# MainPartSCH.net
KiCad netlist of a schematic drawn in Altium Designer
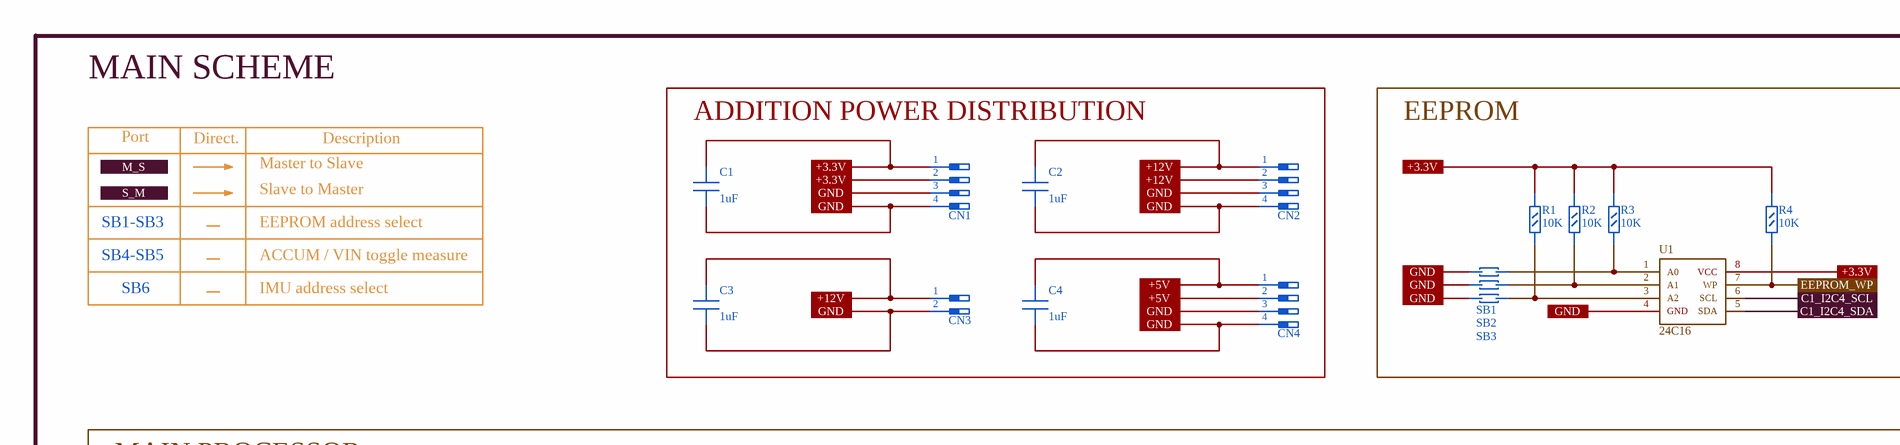
[diagram p0: MainPartSCH.SchDoc, top left]
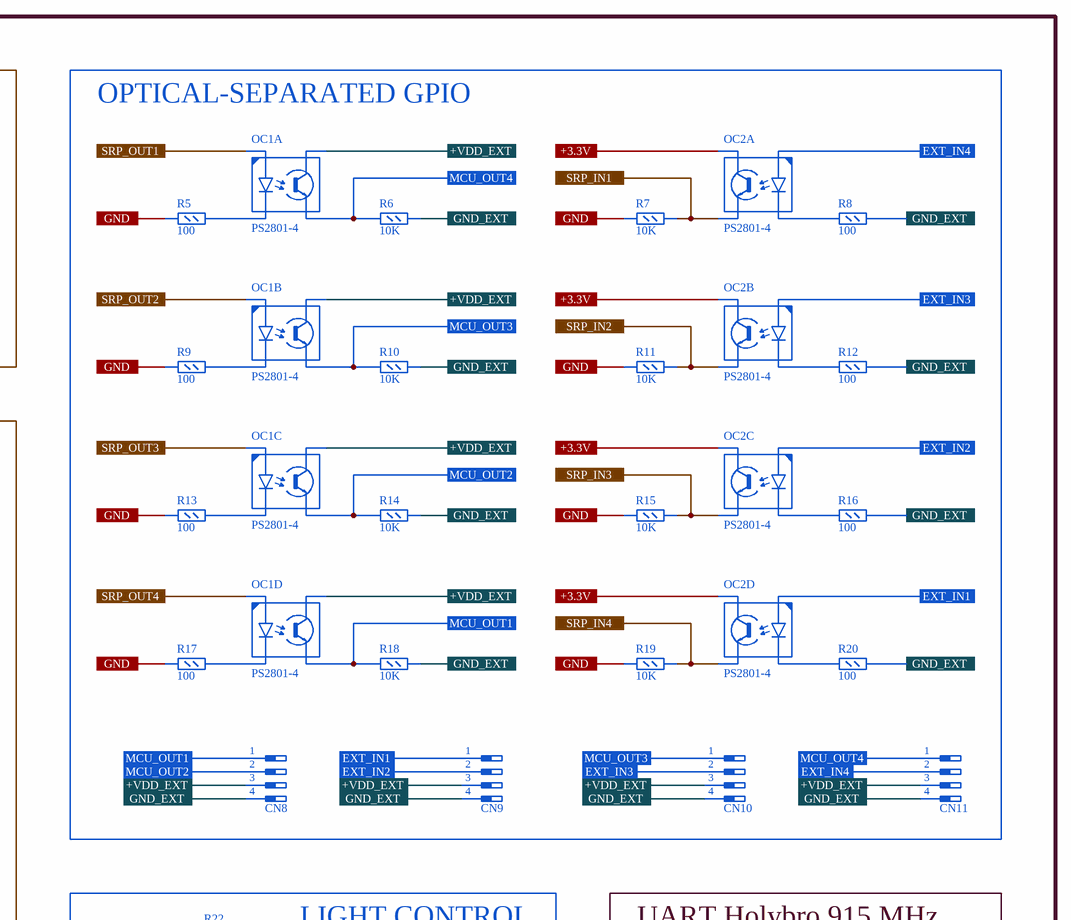
[diagram p1: MainPartSCH.SchDoc, top right]
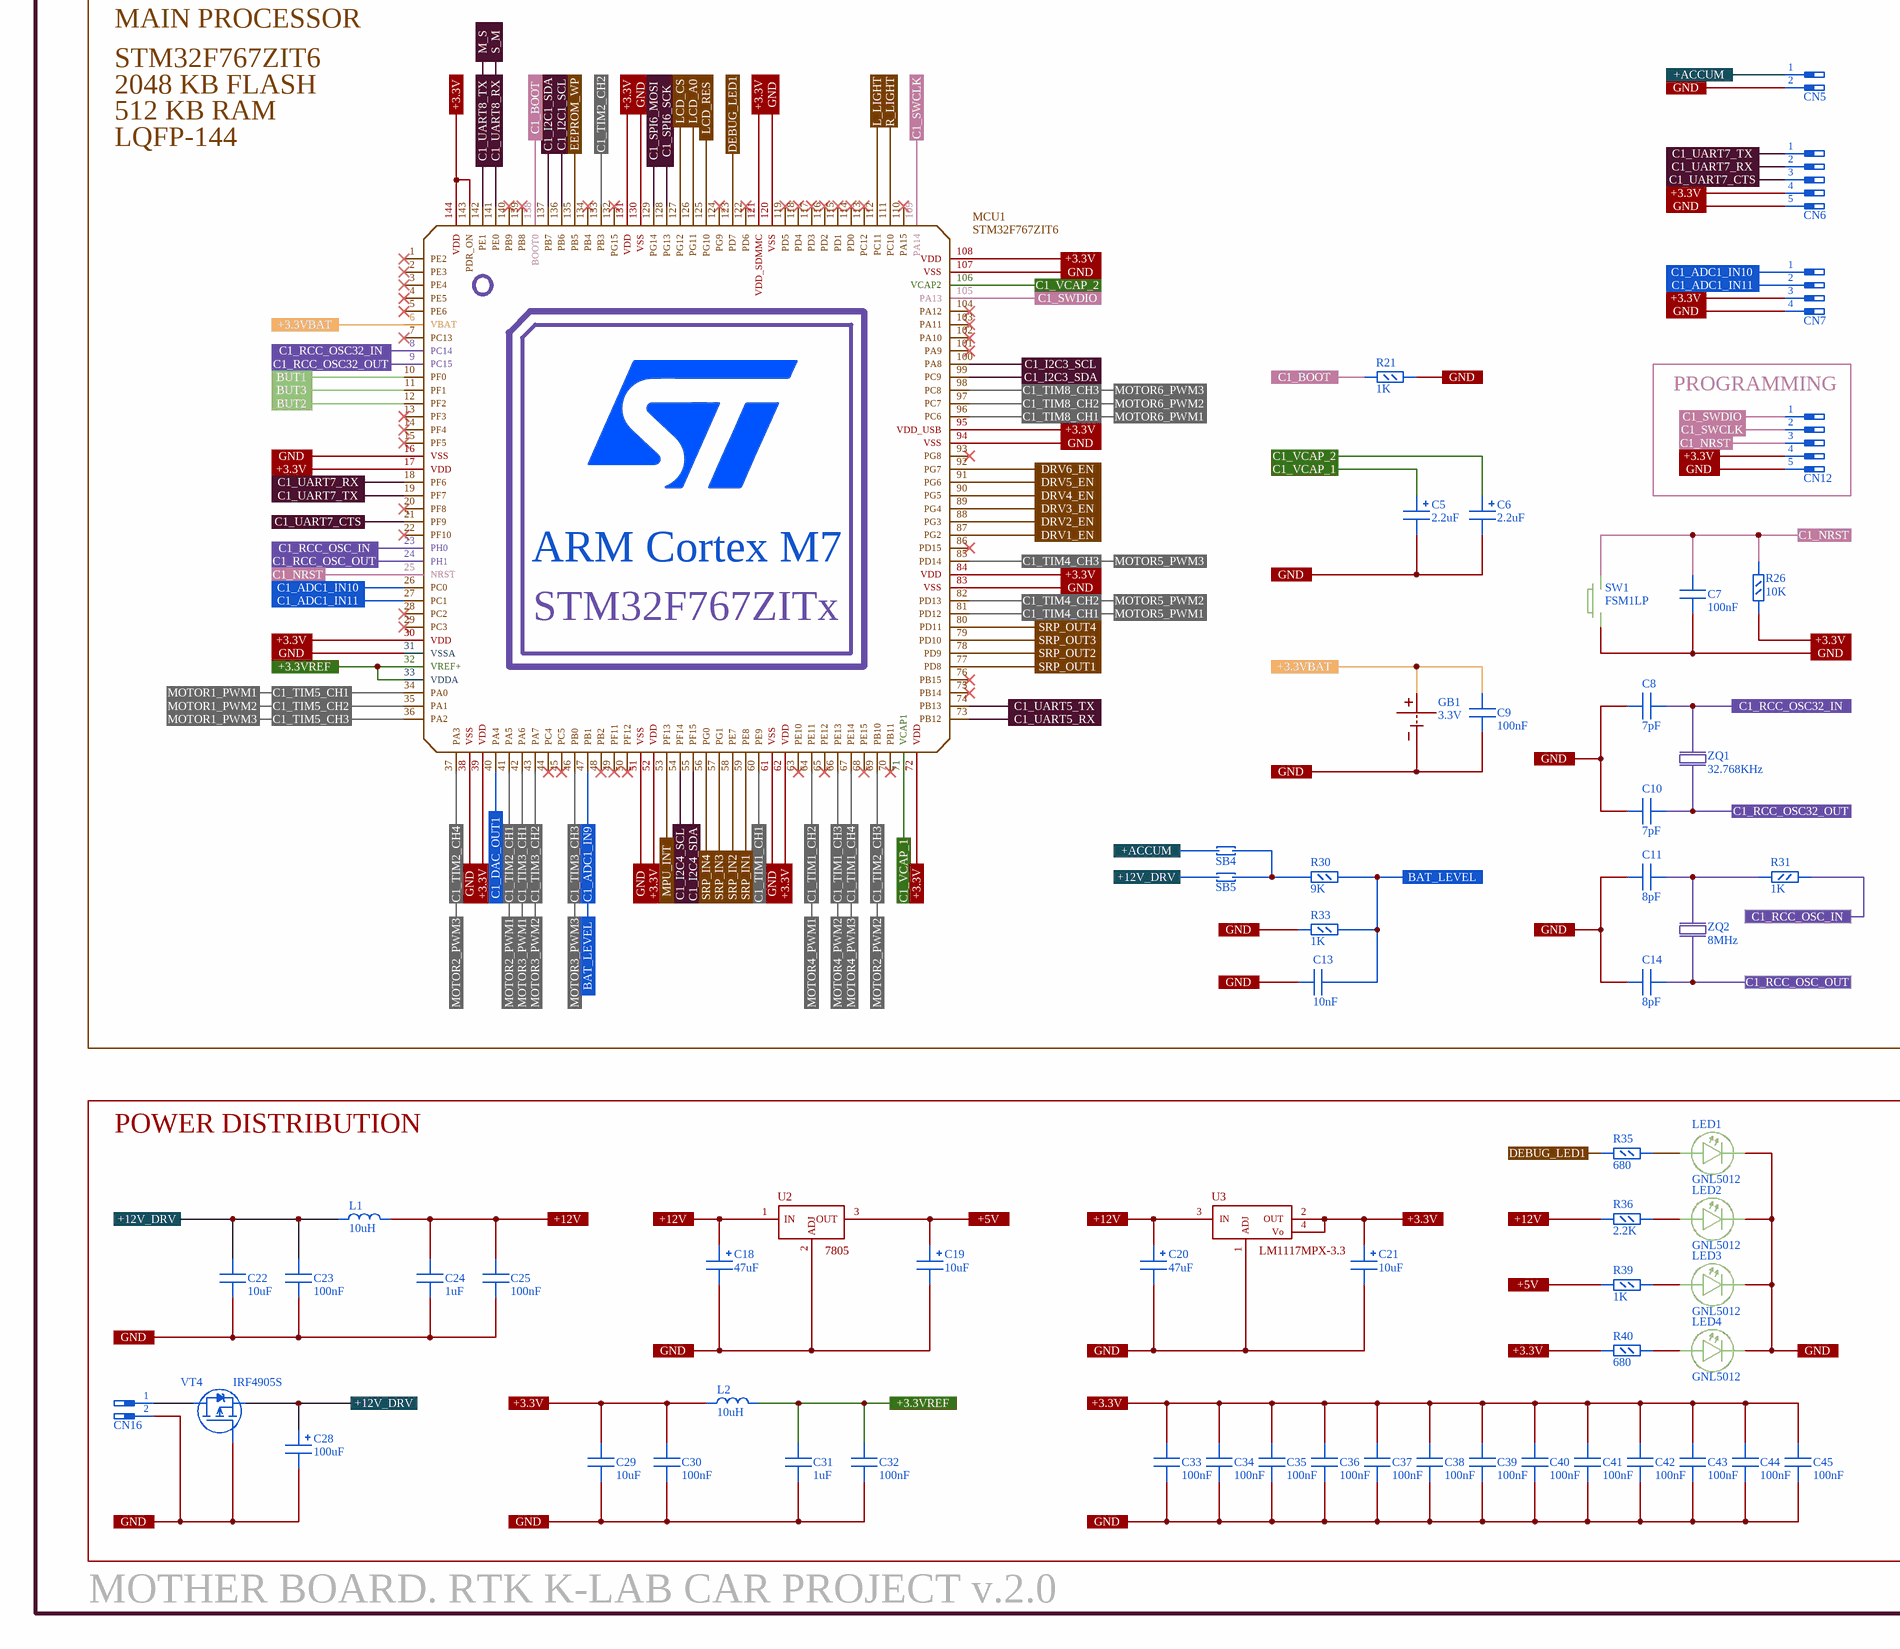
[diagram p2: MainPartSCH.SchDoc, bottom left]
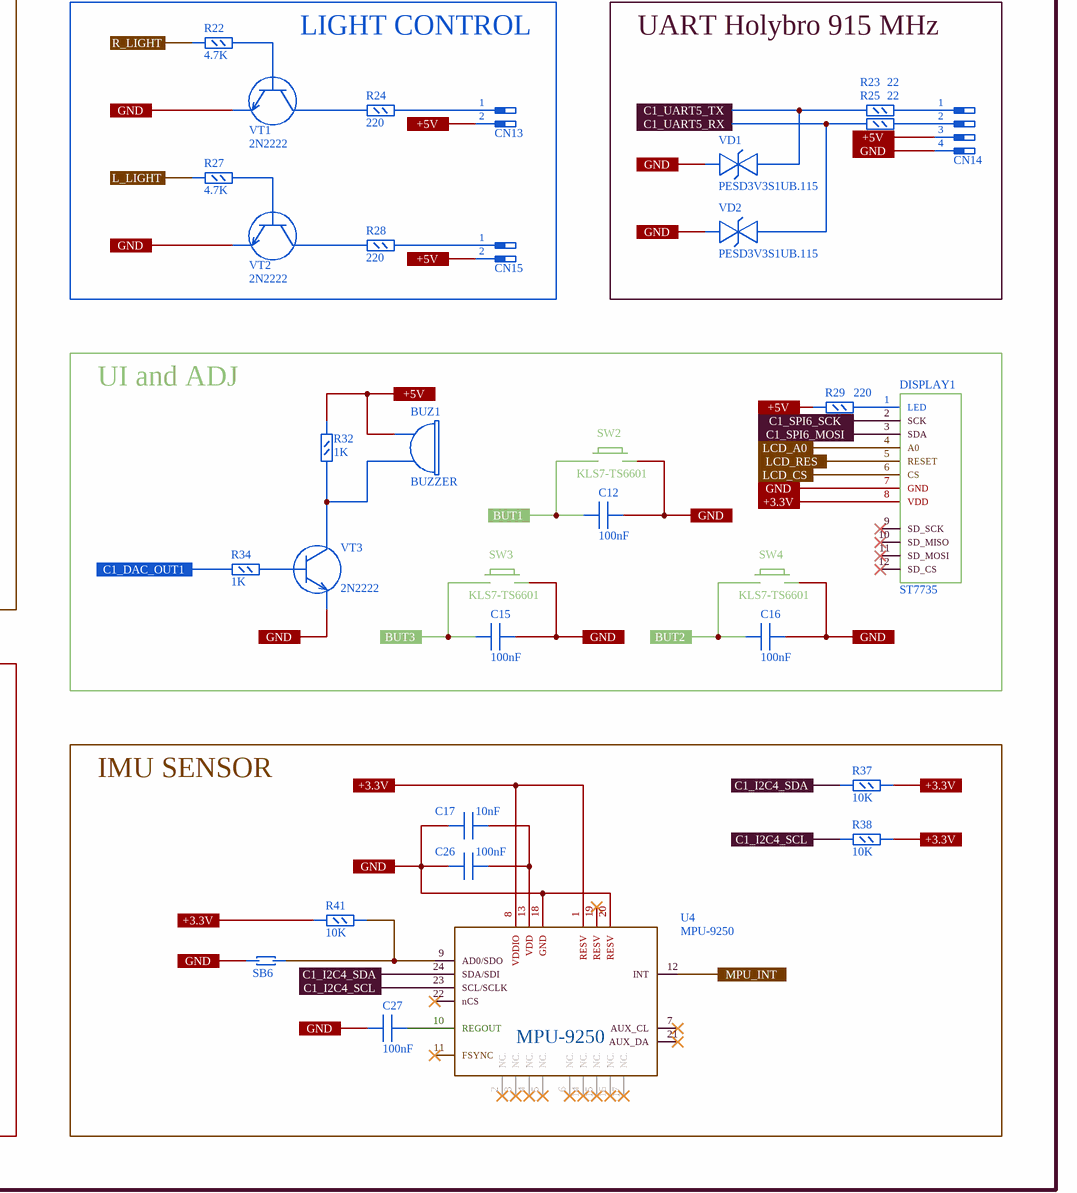
[diagram p3: MainPartSCH.SchDoc, bottom right]

(export (version "E")
  (design (tool "Eeschema 10.0.6"))
  (components
    (comp (ref "BUZ1")
      (value "BUZZER")
      (footprint "BUZZER-5.08MM-D10.5MM")
      (libsource (lib "CommonElements") (part "Buzzer"))
    )
    (comp (ref "C1") (value "1uF") (footprint "C0805") (libsource (lib "CommonElements") (part "Cap")))
    (comp (ref "C2") (value "1uF") (footprint "C0805") (libsource (lib "CommonElements") (part "Cap")))
    (comp (ref "C3") (value "1uF") (footprint "C0805") (libsource (lib "CommonElements") (part "Cap")))
    (comp (ref "C4") (value "1uF") (footprint "C0805") (libsource (lib "CommonElements") (part "Cap")))
    (comp (ref "C5")
      (value "2.2uF")
      (footprint "CAP_TAN-A")
      (libsource (lib "CustomMillLib_Col") (part "Cap_Pol"))
    )
    (comp (ref "C6")
      (value "2.2uF")
      (footprint "CAP_TAN-A")
      (libsource (lib "CustomMillLib_Col") (part "Cap_Pol"))
    )
    (comp (ref "C7") (value "100nF") (footprint "C0603") (libsource (lib "CommonElements") (part "Cap")))
    (comp (ref "C8") (value "7pF") (footprint "C0402") (libsource (lib "CommonElements") (part "Cap")))
    (comp (ref "C9") (value "100nF") (footprint "C0603") (libsource (lib "CommonElements") (part "Cap")))
    (comp (ref "C10") (value "7pF") (footprint "C0402") (libsource (lib "CommonElements") (part "Cap")))
    (comp (ref "C11") (value "8pF") (footprint "C0402") (libsource (lib "CommonElements") (part "Cap")))
    (comp (ref "C12") (value "100nF") (footprint "C0603") (libsource (lib "CommonElements") (part "Cap")))
    (comp (ref "C13") (value "10nF") (footprint "C0603") (libsource (lib "CommonElements") (part "Cap")))
    (comp (ref "C14") (value "8pF") (footprint "C0402") (libsource (lib "CommonElements") (part "Cap")))
    (comp (ref "C15") (value "100nF") (footprint "C0603") (libsource (lib "CommonElements") (part "Cap")))
    (comp (ref "C16") (value "100nF") (footprint "C0603") (libsource (lib "CommonElements") (part "Cap")))
    (comp (ref "C17") (value "10nF") (footprint "C0603") (libsource (lib "CommonElements") (part "Cap")))
    (comp (ref "C18")
      (value "47uF")
      (footprint "CAP_ALSMD-6.3x5.4MM")
      (libsource (lib "CommonElements") (part "Cap Pol"))
    )
    (comp (ref "C19")
      (value "10uF")
      (footprint "CAP_ALSMD-4X5.4MM")
      (libsource (lib "CommonElements") (part "Cap Pol"))
    )
    (comp (ref "C20")
      (value "47uF")
      (footprint "CAP_ALSMD-6.3x5.4MM")
      (libsource (lib "CommonElements") (part "Cap Pol"))
    )
    (comp (ref "C21")
      (value "10uF")
      (footprint "CAP_ALSMD-4X5.4MM")
      (libsource (lib "CommonElements") (part "Cap Pol"))
    )
    (comp (ref "C22") (value "10uF") (footprint "C0805") (libsource (lib "CommonElements") (part "Cap")))
    (comp (ref "C23") (value "100nF") (footprint "C0603") (libsource (lib "CommonElements") (part "Cap")))
    (comp (ref "C24") (value "1uF") (footprint "C0805") (libsource (lib "CommonElements") (part "Cap")))
    (comp (ref "C25") (value "100nF") (footprint "C0603") (libsource (lib "CommonElements") (part "Cap")))
    (comp (ref "C26") (value "100nF") (footprint "C0603") (libsource (lib "CommonElements") (part "Cap")))
    (comp (ref "C27") (value "100nF") (footprint "C0603") (libsource (lib "CommonElements") (part "Cap")))
    (comp (ref "C28")
      (value "100uF")
      (footprint "CAP_ALSMD-8X10.5MM")
      (libsource (lib "CommonElements") (part "Cap Pol"))
    )
    (comp (ref "C29") (value "10uF") (footprint "C0805") (libsource (lib "CommonElements") (part "Cap")))
    (comp (ref "C30") (value "100nF") (footprint "C0603") (libsource (lib "CommonElements") (part "Cap")))
    (comp (ref "C31") (value "1uF") (footprint "C0805") (libsource (lib "CommonElements") (part "Cap")))
    (comp (ref "C32") (value "100nF") (footprint "C0603") (libsource (lib "CommonElements") (part "Cap")))
    (comp (ref "C33") (value "100nF") (footprint "C0603") (libsource (lib "CommonElements") (part "Cap")))
    (comp (ref "C34") (value "100nF") (footprint "C0603") (libsource (lib "CommonElements") (part "Cap")))
    (comp (ref "C35") (value "100nF") (footprint "C0603") (libsource (lib "CommonElements") (part "Cap")))
    (comp (ref "C36") (value "100nF") (footprint "C0603") (libsource (lib "CommonElements") (part "Cap")))
    (comp (ref "C37") (value "100nF") (footprint "C0603") (libsource (lib "CommonElements") (part "Cap")))
    (comp (ref "C38") (value "100nF") (footprint "C0603") (libsource (lib "CommonElements") (part "Cap")))
    (comp (ref "C39") (value "100nF") (footprint "C0603") (libsource (lib "CommonElements") (part "Cap")))
    (comp (ref "C40") (value "100nF") (footprint "C0603") (libsource (lib "CommonElements") (part "Cap")))
    (comp (ref "C41") (value "100nF") (footprint "C0603") (libsource (lib "CommonElements") (part "Cap")))
    (comp (ref "C42") (value "100nF") (footprint "C0603") (libsource (lib "CommonElements") (part "Cap")))
    (comp (ref "C43") (value "100nF") (footprint "C0603") (libsource (lib "CommonElements") (part "Cap")))
    (comp (ref "C44") (value "100nF") (footprint "C0603") (libsource (lib "CommonElements") (part "Cap")))
    (comp (ref "C45") (value "100nF") (footprint "C0603") (libsource (lib "CommonElements") (part "Cap")))
    (comp (ref "CN1") (value "1x04") (footprint "XH2.54-4PIN") (libsource (lib "Connectors") (part "1x04")))
    (comp (ref "CN2") (value "1x04") (footprint "XH2.54-4PIN") (libsource (lib "Connectors") (part "1x04")))
    (comp (ref "CN3") (value "1x02") (footprint "XH2.54-2PIN") (libsource (lib "Connectors") (part "1x02")))
    (comp (ref "CN4") (value "1x04") (footprint "XH2.54-4PIN") (libsource (lib "Connectors") (part "1x04")))
    (comp (ref "CN5") (value "1x02") (footprint "2X1F") (libsource (lib "Connectors") (part "1x02")))
    (comp (ref "CN6") (value "1x05") (footprint "5X1F") (libsource (lib "Connectors") (part "1x05")))
    (comp (ref "CN7") (value "1x04") (footprint "4X1F") (libsource (lib "Connectors") (part "1x04")))
    (comp (ref "CN8") (value "1x04") (footprint "XH2.54-4PIN") (libsource (lib "Connectors") (part "1x04")))
    (comp (ref "CN9") (value "1x04") (footprint "XH2.54-4PIN") (libsource (lib "Connectors") (part "1x04")))
    (comp (ref "CN10") (value "1x04") (footprint "XH2.54-4PIN") (libsource (lib "Connectors") (part "1x04")))
    (comp (ref "CN11") (value "1x04") (footprint "XH2.54-4PIN") (libsource (lib "Connectors") (part "1x04")))
    (comp (ref "CN12") (value "1x05") (footprint "5X1M") (libsource (lib "Connectors") (part "1x05")))
    (comp (ref "CN13") (value "1x02") (footprint "2X1F") (libsource (lib "Connectors") (part "1x02")))
    (comp (ref "CN14") (value "1x04") (footprint "XH2.54-4PIN") (libsource (lib "Connectors") (part "1x04")))
    (comp (ref "CN15") (value "1x02") (footprint "2X1F") (libsource (lib "Connectors") (part "1x02")))
    (comp (ref "CN16") (value "1x02") (footprint "H2-5.08") (libsource (lib "Connectors") (part "1x02")))
    (comp (ref "DISPLAY1")
      (value "ST7735")
      (footprint "8X1M")
      (description "120x160 LCD Display")
      (libsource (lib "OtherEquipmentLib_Col") (part "ST7735 SPI Display + SD Card"))
    )
    (comp (ref "GB1")
      (value "3.3V")
      (footprint "CR1616-SMD")
      (libsource (lib "PowerSupplies_Col") (part "Battery"))
    )
    (comp (ref "L1") (value "10uH") (footprint "L1206") (libsource (lib "CommonElements") (part "Inductor")))
    (comp (ref "L2") (value "10uH") (footprint "L0805") (libsource (lib "CommonElements") (part "Inductor")))
    (comp (ref "LED1")
      (value "GNL5012")
      (footprint "LED0603")
      (libsource (lib "CommonElements") (part "LED"))
    )
    (comp (ref "LED2")
      (value "GNL5012")
      (footprint "LED0603")
      (libsource (lib "CommonElements") (part "LED"))
    )
    (comp (ref "LED3")
      (value "GNL5012")
      (footprint "LED0603")
      (libsource (lib "CommonElements") (part "LED"))
    )
    (comp (ref "LED4")
      (value "GNL5012")
      (footprint "LED0603")
      (libsource (lib "CommonElements") (part "LED"))
    )
    (comp (ref "MCU1")
      (value "STM32F767ZIT6")
      (footprint "LQFP144")
      (libsource (lib "STM32") (part "STM32F767ZITx"))
    )
    (comp (ref "OC1")
      (value "PS2801-4")
      (footprint "SSOP16")
      (libsource (lib "CommonElements") (part "Optocoupler-4"))
    )
    (comp (ref "OC2") (value "PS2801-4") (footprint "SSOP16") (libsource (lib "") (part "Optocoupler-4_1")))
    (comp (ref "R1") (value "10K") (footprint "R0603") (libsource (lib "CommonElements") (part "Res")))
    (comp (ref "R2") (value "10K") (footprint "R0603") (libsource (lib "CommonElements") (part "Res")))
    (comp (ref "R3") (value "10K") (footprint "R0603") (libsource (lib "CommonElements") (part "Res")))
    (comp (ref "R4") (value "10K") (footprint "R0603") (libsource (lib "CommonElements") (part "Res")))
    (comp (ref "R5") (value "100") (footprint "R0603") (libsource (lib "CommonElements") (part "Res")))
    (comp (ref "R6") (value "10K") (footprint "R0603") (libsource (lib "CommonElements") (part "Res")))
    (comp (ref "R7") (value "10K") (footprint "R0603") (libsource (lib "CommonElements") (part "Res")))
    (comp (ref "R8") (value "100") (footprint "R0603") (libsource (lib "CommonElements") (part "Res")))
    (comp (ref "R9") (value "100") (footprint "R0603") (libsource (lib "CommonElements") (part "Res")))
    (comp (ref "R10") (value "10K") (footprint "R0603") (libsource (lib "CommonElements") (part "Res")))
    (comp (ref "R11") (value "10K") (footprint "R0603") (libsource (lib "CommonElements") (part "Res")))
    (comp (ref "R12") (value "100") (footprint "R0603") (libsource (lib "CommonElements") (part "Res")))
    (comp (ref "R13") (value "100") (footprint "R0603") (libsource (lib "CommonElements") (part "Res")))
    (comp (ref "R14") (value "10K") (footprint "R0603") (libsource (lib "CommonElements") (part "Res")))
    (comp (ref "R15") (value "10K") (footprint "R0603") (libsource (lib "CommonElements") (part "Res")))
    (comp (ref "R16") (value "100") (footprint "R0603") (libsource (lib "CommonElements") (part "Res")))
    (comp (ref "R17") (value "100") (footprint "R0603") (libsource (lib "CommonElements") (part "Res")))
    (comp (ref "R18") (value "10K") (footprint "R0603") (libsource (lib "CommonElements") (part "Res")))
    (comp (ref "R19") (value "10K") (footprint "R0603") (libsource (lib "CommonElements") (part "Res")))
    (comp (ref "R20") (value "100") (footprint "R0603") (libsource (lib "CommonElements") (part "Res")))
    (comp (ref "R21") (value "1K") (footprint "R0603") (libsource (lib "CommonElements") (part "Res")))
    (comp (ref "R22") (value "4.7K") (footprint "R0603") (libsource (lib "CommonElements") (part "Res")))
    (comp (ref "R23") (value "22") (footprint "R0805") (libsource (lib "CommonElements") (part "Res")))
    (comp (ref "R24") (value "220") (footprint "R0603") (libsource (lib "CommonElements") (part "Res")))
    (comp (ref "R25") (value "22") (footprint "R0805") (libsource (lib "CommonElements") (part "Res")))
    (comp (ref "R26") (value "10K") (footprint "R0603") (libsource (lib "CommonElements") (part "Res")))
    (comp (ref "R27") (value "4.7K") (footprint "R0603") (libsource (lib "CommonElements") (part "Res")))
    (comp (ref "R28") (value "220") (footprint "R0603") (libsource (lib "CommonElements") (part "Res")))
    (comp (ref "R29") (value "220") (footprint "R0603") (libsource (lib "CommonElements") (part "Res")))
    (comp (ref "R30") (value "9K") (footprint "R0603") (libsource (lib "CommonElements") (part "Res")))
    (comp (ref "R31") (value "1K") (footprint "R0603") (libsource (lib "CommonElements") (part "Res")))
    (comp (ref "R32") (value "1K") (footprint "R0603") (libsource (lib "CommonElements") (part "Res")))
    (comp (ref "R33") (value "1K") (footprint "R0603") (libsource (lib "CommonElements") (part "Res")))
    (comp (ref "R34") (value "1K") (footprint "R0603") (libsource (lib "CommonElements") (part "Res")))
    (comp (ref "R35") (value "680") (footprint "R0603") (libsource (lib "CommonElements") (part "Res")))
    (comp (ref "R36") (value "2.2K") (footprint "R0603") (libsource (lib "CommonElements") (part "Res")))
    (comp (ref "R37") (value "10K") (footprint "R0603") (libsource (lib "CommonElements") (part "Res")))
    (comp (ref "R38") (value "10K") (footprint "R0603") (libsource (lib "CommonElements") (part "Res")))
    (comp (ref "R39") (value "1K") (footprint "R0603") (libsource (lib "CommonElements") (part "Res")))
    (comp (ref "R40") (value "680") (footprint "R0603") (libsource (lib "CommonElements") (part "Res")))
    (comp (ref "R41") (value "10K") (footprint "R0603") (libsource (lib "CommonElements") (part "Res")))
    (comp (ref "SB1")
      (value "Soldier Bridge")
      (footprint "SOLDBR")
      (libsource (lib "CommonElements") (part "Soldier Bridge"))
    )
    (comp (ref "SB2")
      (value "Soldier Bridge")
      (footprint "SOLDBR")
      (libsource (lib "CommonElements") (part "Soldier Bridge"))
    )
    (comp (ref "SB3")
      (value "Soldier Bridge")
      (footprint "SOLDBR")
      (libsource (lib "CommonElements") (part "Soldier Bridge"))
    )
    (comp (ref "SB4")
      (value "Soldier Bridge")
      (footprint "SOLDBR")
      (libsource (lib "CommonElements") (part "Soldier Bridge"))
    )
    (comp (ref "SB5")
      (value "Soldier Bridge")
      (footprint "SOLDBR")
      (libsource (lib "CommonElements") (part "Soldier Bridge"))
    )
    (comp (ref "SB6")
      (value "Soldier Bridge")
      (footprint "SOLDBR")
      (libsource (lib "CommonElements") (part "Soldier Bridge"))
    )
    (comp (ref "SW1")
      (value "FSM1LP")
      (footprint "BUT-SMD-8X6.2MM")
      (libsource (lib "CommonElements") (part "Button"))
    )
    (comp (ref "SW2")
      (value "KLS7-TS6601")
      (footprint "BUT-6.5X4.5MM")
      (libsource (lib "CommonElements") (part "Button"))
    )
    (comp (ref "SW3")
      (value "KLS7-TS6601")
      (footprint "BUT-6.5X4.5MM")
      (libsource (lib "CommonElements") (part "Button"))
    )
    (comp (ref "SW4")
      (value "KLS7-TS6601")
      (footprint "BUT-6.5X4.5MM")
      (libsource (lib "CommonElements") (part "Button"))
    )
    (comp (ref "U1")
      (value "24C16")
      (footprint "SOIC8")
      (description "Two-Wire I2C Serial EEPROM")
      (libsource (lib "DigitalUnits") (part "24C16"))
    )
    (comp (ref "U2") (value "7805") (footprint "SOT-223") (libsource (lib "Power") (part "LM7805")))
    (comp (ref "U3") (value "LM1117MPX-3.3") (footprint "SOT-223") (libsource (lib "Power") (part "LM1117")))
    (comp (ref "U4")
      (value "MPU-9250")
      (footprint "QFN24")
      (libsource (lib "DigitalUnits") (part "MPU-9250"))
    )
    (comp (ref "VD1")
      (value "PESD3V3S1UB.115")
      (footprint "SOD-323")
      (libsource (lib "CommonElements") (part "Suppressor"))
    )
    (comp (ref "VD2")
      (value "PESD3V3S1UB.115")
      (footprint "SOD-323")
      (libsource (lib "CommonElements") (part "Suppressor"))
    )
    (comp (ref "VT1")
      (value "2N2222")
      (footprint "SOT-23-123")
      (libsource (lib "CommonElements") (part "NPN"))
    )
    (comp (ref "VT2")
      (value "2N2222")
      (footprint "SOT-23-123")
      (libsource (lib "CommonElements") (part "NPN"))
    )
    (comp (ref "VT3")
      (value "2N2222")
      (footprint "SOT-23-123")
      (libsource (lib "CommonElements") (part "NPN"))
    )
    (comp (ref "VT4")
      (value "IRF4905S")
      (footprint "D2PAK")
      (libsource (lib "CommonElements") (part "MOSFET-P"))
    )
    (comp (ref "ZQ1")
      (value "32.768KHz")
      (footprint "NX3215SA")
      (libsource (lib "CommonElements") (part "Crystall"))
    )
    (comp (ref "ZQ2")
      (value "8MHz")
      (footprint "NX5032GA")
      (libsource (lib "CommonElements") (part "Crystall"))
    )
  )
  (nets
    (net (code "1") (name "/+3.3V") (class "Default")
      (node (ref "C1") (pin "2") (pinfunction "62_2") (pintype "passive"))
      (node (ref "C21") (pin "1") (pinfunction "61_1") (pintype "passive"))
      (node (ref "C29") (pin "2") (pinfunction "62_2") (pintype "passive"))
      (node (ref "C30") (pin "2") (pinfunction "62_2") (pintype "passive"))
      (node (ref "C33") (pin "2") (pinfunction "62_2") (pintype "passive"))
      (node (ref "C34") (pin "2") (pinfunction "62_2") (pintype "passive"))
      (node (ref "C35") (pin "2") (pinfunction "62_2") (pintype "passive"))
      (node (ref "C36") (pin "2") (pinfunction "62_2") (pintype "passive"))
      (node (ref "C37") (pin "2") (pinfunction "62_2") (pintype "passive"))
      (node (ref "C38") (pin "2") (pinfunction "62_2") (pintype "passive"))
      (node (ref "C39") (pin "2") (pinfunction "62_2") (pintype "passive"))
      (node (ref "C40") (pin "2") (pinfunction "62_2") (pintype "passive"))
      (node (ref "C41") (pin "2") (pinfunction "62_2") (pintype "passive"))
      (node (ref "C42") (pin "2") (pinfunction "62_2") (pintype "passive"))
      (node (ref "C43") (pin "2") (pinfunction "62_2") (pintype "passive"))
      (node (ref "C44") (pin "2") (pinfunction "62_2") (pintype "passive"))
      (node (ref "C45") (pin "2") (pinfunction "62_2") (pintype "passive"))
      (node (ref "CN1") (pin "1") (pintype "passive"))
      (node (ref "CN1") (pin "2") (pintype "passive"))
      (node (ref "CN12") (pin "4") (pintype "passive"))
      (node (ref "CN6") (pin "4") (pintype "passive"))
      (node (ref "CN7") (pin "3") (pintype "passive"))
      (node (ref "DISPLAY1") (pin "8") (pinfunction "VDD_8") (pintype "passive"))
      (node (ref "L2") (pin "1") (pinfunction "3_1") (pintype "passive"))
      (node (ref "MCU1") (pin "108") (pinfunction "VDD_108") (pintype "passive"))
      (node (ref "MCU1") (pin "121") (pinfunction "VDD_SDMMC_121") (pintype "passive"))
      (node (ref "MCU1") (pin "131") (pinfunction "VDD_131") (pintype "passive"))
      (node (ref "MCU1") (pin "143") (pinfunction "PDR_ON_143") (pintype "passive"))
      (node (ref "MCU1") (pin "144") (pinfunction "VDD_144") (pintype "passive"))
      (node (ref "MCU1") (pin "17") (pinfunction "VDD_17") (pintype "passive"))
      (node (ref "MCU1") (pin "30") (pinfunction "VDD_30") (pintype "passive"))
      (node (ref "MCU1") (pin "39") (pinfunction "VDD_39") (pintype "passive"))
      (node (ref "MCU1") (pin "52") (pinfunction "VDD_52") (pintype "passive"))
      (node (ref "MCU1") (pin "62") (pinfunction "VDD_62") (pintype "passive"))
      (node (ref "MCU1") (pin "72") (pinfunction "VDD_72") (pintype "passive"))
      (node (ref "MCU1") (pin "84") (pinfunction "VDD_84") (pintype "passive"))
      (node (ref "MCU1") (pin "95") (pinfunction "VDD_USB_95") (pintype "passive"))
      (node (ref "OC2") (pin "10") (pinfunction "4_10") (pintype "passive"))
      (node (ref "OC2") (pin "12") (pinfunction "4_12") (pintype "passive"))
      (node (ref "OC2") (pin "14") (pinfunction "4_14") (pintype "passive"))
      (node (ref "OC2") (pin "16") (pinfunction "4_16") (pintype "passive"))
      (node (ref "R1") (pin "2") (pinfunction "2_2") (pintype "passive"))
      (node (ref "R2") (pin "2") (pinfunction "2_2") (pintype "passive"))
      (node (ref "R26") (pin "2") (pinfunction "2_2") (pintype "passive"))
      (node (ref "R3") (pin "2") (pinfunction "2_2") (pintype "passive"))
      (node (ref "R37") (pin "2") (pinfunction "2_2") (pintype "passive"))
      (node (ref "R38") (pin "2") (pinfunction "2_2") (pintype "passive"))
      (node (ref "R4") (pin "2") (pinfunction "2_2") (pintype "passive"))
      (node (ref "R40") (pin "2") (pinfunction "2_2") (pintype "passive"))
      (node (ref "R41") (pin "2") (pinfunction "2_2") (pintype "passive"))
      (node (ref "U1") (pin "8") (pinfunction "VCC_8") (pintype "passive"))
      (node (ref "U3") (pin "2") (pinfunction "OUT_2") (pintype "passive"))
      (node (ref "U3") (pin "4") (pinfunction "Vo_4") (pintype "passive"))
      (node (ref "U4") (pin "1") (pinfunction "RESV_1") (pintype "passive"))
      (node (ref "U4") (pin "8") (pinfunction "VDDIO_8") (pintype "passive"))
    )
    (net (code "2") (name "/+3.3VBAT") (class "Default")
      (node (ref "C9") (pin "1") (pinfunction "61_1") (pintype "passive"))
      (node (ref "GB1") (pin "2") (pintype "passive"))
      (node (ref "MCU1") (pin "6") (pinfunction "VBAT_6") (pintype "passive"))
    )
    (net (code "3") (name "/+3.3VREF") (class "Default")
      (node (ref "C31") (pin "2") (pinfunction "62_2") (pintype "passive"))
      (node (ref "C32") (pin "2") (pinfunction "62_2") (pintype "passive"))
      (node (ref "L2") (pin "2") (pinfunction "4_2") (pintype "passive"))
      (node (ref "MCU1") (pin "32") (pinfunction "VREF+_32") (pintype "passive"))
      (node (ref "MCU1") (pin "33") (pinfunction "VDDA_33") (pintype "passive"))
    )
    (net (code "4") (name "/+5V") (class "Default")
      (node (ref "BUZ1") (pin "1") (pintype "passive"))
      (node (ref "C19") (pin "1") (pinfunction "61_1") (pintype "passive"))
      (node (ref "C4") (pin "2") (pinfunction "62_2") (pintype "passive"))
      (node (ref "CN13") (pin "2") (pintype "passive"))
      (node (ref "CN14") (pin "3") (pintype "passive"))
      (node (ref "CN15") (pin "2") (pintype "passive"))
      (node (ref "CN4") (pin "1") (pintype "passive"))
      (node (ref "CN4") (pin "2") (pintype "passive"))
      (node (ref "R29") (pin "1") (pinfunction "2_1") (pintype "passive"))
      (node (ref "R32") (pin "2") (pinfunction "2_2") (pintype "passive"))
      (node (ref "R39") (pin "2") (pinfunction "2_2") (pintype "passive"))
      (node (ref "U2") (pin "3") (pinfunction "OUT_3") (pintype "passive"))
    )
    (net (code "5") (name "/+12V") (class "Default")
      (node (ref "C18") (pin "1") (pinfunction "61_1") (pintype "passive"))
      (node (ref "C2") (pin "2") (pinfunction "62_2") (pintype "passive"))
      (node (ref "C20") (pin "1") (pinfunction "61_1") (pintype "passive"))
      (node (ref "C24") (pin "2") (pinfunction "62_2") (pintype "passive"))
      (node (ref "C25") (pin "2") (pinfunction "62_2") (pintype "passive"))
      (node (ref "C3") (pin "2") (pinfunction "62_2") (pintype "passive"))
      (node (ref "CN2") (pin "1") (pintype "passive"))
      (node (ref "CN2") (pin "2") (pintype "passive"))
      (node (ref "CN3") (pin "1") (pintype "passive"))
      (node (ref "L1") (pin "2") (pinfunction "4_2") (pintype "passive"))
      (node (ref "R36") (pin "2") (pinfunction "2_2") (pintype "passive"))
      (node (ref "U2") (pin "1") (pinfunction "IN_1") (pintype "passive"))
      (node (ref "U3") (pin "3") (pinfunction "IN_3") (pintype "passive"))
    )
    (net (code "6") (name "/+12V_DRV") (class "Default")
      (node (ref "C22") (pin "2") (pinfunction "62_2") (pintype "passive"))
      (node (ref "C23") (pin "2") (pinfunction "62_2") (pintype "passive"))
      (node (ref "C28") (pin "1") (pinfunction "61_1") (pintype "passive"))
      (node (ref "L1") (pin "1") (pinfunction "3_1") (pintype "passive"))
      (node (ref "SB5") (pin "1") (pintype "passive"))
      (node (ref "VT4") (pin "3") (pinfunction "S_3") (pintype "passive"))
    )
    (net (code "7") (name "/+ACCUM") (class "Default")
      (node (ref "CN5") (pin "1") (pintype "passive"))
      (node (ref "SB4") (pin "1") (pintype "passive"))
    )
    (net (code "8") (name "/+VDD_EXT") (class "Default")
      (node (ref "CN10") (pin "3") (pintype "passive"))
      (node (ref "CN11") (pin "3") (pintype "passive"))
      (node (ref "CN8") (pin "3") (pintype "passive"))
      (node (ref "CN9") (pin "3") (pintype "passive"))
      (node (ref "OC1") (pin "10") (pinfunction "4_10") (pintype "passive"))
      (node (ref "OC1") (pin "12") (pinfunction "4_12") (pintype "passive"))
      (node (ref "OC1") (pin "14") (pinfunction "4_14") (pintype "passive"))
      (node (ref "OC1") (pin "16") (pinfunction "4_16") (pintype "passive"))
    )
    (net (code "9") (name "/BAT_LEVEL") (class "Default")
      (node (ref "C13") (pin "2") (pinfunction "62_2") (pintype "passive"))
      (node (ref "MCU1") (pin "47") (pinfunction "PB1_47") (pintype "passive"))
      (node (ref "R30") (pin "2") (pinfunction "2_2") (pintype "passive"))
      (node (ref "R33") (pin "2") (pinfunction "2_2") (pintype "passive"))
    )
    (net (code "10") (name "/BUT1") (class "Default")
      (node (ref "C12") (pin "2") (pinfunction "62_2") (pintype "passive"))
      (node (ref "MCU1") (pin "10") (pinfunction "PF0_10") (pintype "passive"))
      (node (ref "SW2") (pin "1") (pinfunction "Q1_1") (pintype "passive"))
    )
    (net (code "11") (name "/BUT2") (class "Default")
      (node (ref "C16") (pin "2") (pinfunction "62_2") (pintype "passive"))
      (node (ref "MCU1") (pin "12") (pinfunction "PF2_12") (pintype "passive"))
      (node (ref "SW4") (pin "1") (pinfunction "Q1_1") (pintype "passive"))
    )
    (net (code "12") (name "/BUT3") (class "Default")
      (node (ref "C15") (pin "2") (pinfunction "62_2") (pintype "passive"))
      (node (ref "MCU1") (pin "11") (pinfunction "PF1_11") (pintype "passive"))
      (node (ref "SW3") (pin "1") (pinfunction "Q1_1") (pintype "passive"))
    )
    (net (code "13") (name "/C1_ADC1_IN10") (class "Default")
      (node (ref "CN7") (pin "1") (pintype "passive"))
      (node (ref "MCU1") (pin "26") (pinfunction "PC0_26") (pintype "passive"))
    )
    (net (code "14") (name "/C1_ADC1_IN11") (class "Default")
      (node (ref "CN7") (pin "2") (pintype "passive"))
      (node (ref "MCU1") (pin "27") (pinfunction "PC1_27") (pintype "passive"))
    )
    (net (code "15") (name "/C1_BOOT") (class "Default")
      (node (ref "MCU1") (pin "138") (pinfunction "BOOT0_138") (pintype "passive"))
      (node (ref "R21") (pin "2") (pinfunction "2_2") (pintype "passive"))
    )
    (net (code "16") (name "/C1_DAC_OUT1") (class "Default")
      (node (ref "MCU1") (pin "40") (pinfunction "PA4_40") (pintype "passive"))
      (node (ref "R34") (pin "1") (pinfunction "2_1") (pintype "passive"))
    )
    (net (code "17") (name "/C1_I2C1_SCL") (class "Default")
      (node (ref "MCU1") (pin "136") (pinfunction "PB6_136") (pintype "passive"))
    )
    (net (code "18") (name "/C1_I2C1_SDA") (class "Default")
      (node (ref "MCU1") (pin "137") (pinfunction "PB7_137") (pintype "passive"))
    )
    (net (code "19") (name "/C1_I2C3_SCL") (class "Default")
      (node (ref "MCU1") (pin "100") (pinfunction "PA8_100") (pintype "passive"))
    )
    (net (code "20") (name "/C1_I2C3_SDA") (class "Default")
      (node (ref "MCU1") (pin "99") (pinfunction "PC9_99") (pintype "passive"))
    )
    (net (code "21") (name "/C1_I2C4_SCL") (class "Default")
      (node (ref "MCU1") (pin "54") (pinfunction "PF14_54") (pintype "passive"))
      (node (ref "R38") (pin "1") (pinfunction "2_1") (pintype "passive"))
      (node (ref "U1") (pin "6") (pinfunction "SCL_6") (pintype "passive"))
      (node (ref "U4") (pin "23") (pinfunction "SCL/SCLK_23") (pintype "passive"))
    )
    (net (code "22") (name "/C1_I2C4_SDA") (class "Default")
      (node (ref "MCU1") (pin "55") (pinfunction "PF15_55") (pintype "passive"))
      (node (ref "R37") (pin "1") (pinfunction "2_1") (pintype "passive"))
      (node (ref "U1") (pin "5") (pinfunction "SDA_5") (pintype "passive"))
      (node (ref "U4") (pin "24") (pinfunction "SDA/SDI_24") (pintype "passive"))
    )
    (net (code "23") (name "/C1_NRST") (class "Default")
      (node (ref "C7") (pin "2") (pinfunction "62_2") (pintype "passive"))
      (node (ref "CN12") (pin "3") (pintype "passive"))
      (node (ref "MCU1") (pin "25") (pinfunction "NRST_25") (pintype "passive"))
      (node (ref "R26") (pin "1") (pinfunction "2_1") (pintype "passive"))
      (node (ref "SW1") (pin "3") (pinfunction "Q2_3") (pintype "passive"))
    )
    (net (code "24") (name "/C1_RCC_OSC32_IN") (class "Default")
      (node (ref "C8") (pin "1") (pinfunction "61_1") (pintype "passive"))
      (node (ref "MCU1") (pin "8") (pinfunction "PC14_8") (pintype "passive"))
      (node (ref "ZQ1") (pin "1") (pinfunction "10_1") (pintype "passive"))
    )
    (net (code "25") (name "/C1_RCC_OSC32_OUT") (class "Default")
      (node (ref "C10") (pin "1") (pinfunction "61_1") (pintype "passive"))
      (node (ref "MCU1") (pin "9") (pinfunction "PC15_9") (pintype "passive"))
      (node (ref "ZQ1") (pin "2") (pinfunction "2_2") (pintype "passive"))
    )
    (net (code "26") (name "/C1_RCC_OSC_IN") (class "Default")
      (node (ref "MCU1") (pin "23") (pinfunction "PH0_23") (pintype "passive"))
      (node (ref "R31") (pin "1") (pinfunction "2_1") (pintype "passive"))
    )
    (net (code "27") (name "/C1_RCC_OSC_OUT") (class "Default")
      (node (ref "C14") (pin "1") (pinfunction "61_1") (pintype "passive"))
      (node (ref "MCU1") (pin "24") (pinfunction "PH1_24") (pintype "passive"))
      (node (ref "ZQ2") (pin "2") (pinfunction "2_2") (pintype "passive"))
    )
    (net (code "28") (name "/C1_SPI6_MOSI") (class "Default")
      (node (ref "DISPLAY1") (pin "3") (pinfunction "SDA_3") (pintype "passive"))
      (node (ref "MCU1") (pin "129") (pinfunction "PG14_129") (pintype "passive"))
    )
    (net (code "29") (name "/C1_SPI6_SCK") (class "Default")
      (node (ref "DISPLAY1") (pin "2") (pinfunction "SCK_2") (pintype "passive"))
      (node (ref "MCU1") (pin "128") (pinfunction "PG13_128") (pintype "passive"))
    )
    (net (code "30") (name "/C1_SWCLK") (class "Default")
      (node (ref "CN12") (pin "2") (pintype "passive"))
      (node (ref "MCU1") (pin "109") (pinfunction "PA14_109") (pintype "passive"))
    )
    (net (code "31") (name "/C1_SWDIO") (class "Default")
      (node (ref "CN12") (pin "1") (pintype "passive"))
      (node (ref "MCU1") (pin "105") (pinfunction "PA13_105") (pintype "passive"))
    )
    (net (code "32") (name "/C1_TIM1_CH1") (class "Default")
      (node (ref "MCU1") (pin "60") (pinfunction "PE9_60") (pintype "passive"))
    )
    (net (code "33") (name "/C1_TIM1_CH2") (class "Default")
      (node (ref "MCU1") (pin "64") (pinfunction "PE11_64") (pintype "passive"))
    )
    (net (code "34") (name "/C1_TIM1_CH3") (class "Default")
      (node (ref "MCU1") (pin "66") (pinfunction "PE13_66") (pintype "passive"))
    )
    (net (code "35") (name "/C1_TIM1_CH4") (class "Default")
      (node (ref "MCU1") (pin "67") (pinfunction "PE14_67") (pintype "passive"))
    )
    (net (code "36") (name "/C1_TIM2_CH1") (class "Default")
      (node (ref "MCU1") (pin "41") (pinfunction "PA5_41") (pintype "passive"))
    )
    (net (code "37") (name "/C1_TIM2_CH2") (class "Default")
      (node (ref "MCU1") (pin "133") (pinfunction "PB3_133") (pintype "passive"))
    )
    (net (code "38") (name "/C1_TIM2_CH3") (class "Default")
      (node (ref "MCU1") (pin "69") (pinfunction "PB10_69") (pintype "passive"))
    )
    (net (code "39") (name "/C1_TIM2_CH4") (class "Default")
      (node (ref "MCU1") (pin "37") (pinfunction "PA3_37") (pintype "passive"))
    )
    (net (code "40") (name "/C1_TIM3_CH1") (class "Default")
      (node (ref "MCU1") (pin "42") (pinfunction "PA6_42") (pintype "passive"))
    )
    (net (code "41") (name "/C1_TIM3_CH2") (class "Default")
      (node (ref "MCU1") (pin "43") (pinfunction "PA7_43") (pintype "passive"))
    )
    (net (code "42") (name "/C1_TIM3_CH3") (class "Default")
      (node (ref "MCU1") (pin "46") (pinfunction "PB0_46") (pintype "passive"))
    )
    (net (code "43") (name "/C1_TIM4_CH1") (class "Default")
      (node (ref "MCU1") (pin "81") (pinfunction "PD12_81") (pintype "passive"))
    )
    (net (code "44") (name "/C1_TIM4_CH2") (class "Default")
      (node (ref "MCU1") (pin "82") (pinfunction "PD13_82") (pintype "passive"))
    )
    (net (code "45") (name "/C1_TIM4_CH3") (class "Default")
      (node (ref "MCU1") (pin "85") (pinfunction "PD14_85") (pintype "passive"))
    )
    (net (code "46") (name "/C1_TIM5_CH1") (class "Default")
      (node (ref "MCU1") (pin "34") (pinfunction "PA0_34") (pintype "passive"))
    )
    (net (code "47") (name "/C1_TIM5_CH2") (class "Default")
      (node (ref "MCU1") (pin "35") (pinfunction "PA1_35") (pintype "passive"))
    )
    (net (code "48") (name "/C1_TIM5_CH3") (class "Default")
      (node (ref "MCU1") (pin "36") (pinfunction "PA2_36") (pintype "passive"))
    )
    (net (code "49") (name "/C1_TIM8_CH1") (class "Default")
      (node (ref "MCU1") (pin "96") (pinfunction "PC6_96") (pintype "passive"))
    )
    (net (code "50") (name "/C1_TIM8_CH2") (class "Default")
      (node (ref "MCU1") (pin "97") (pinfunction "PC7_97") (pintype "passive"))
    )
    (net (code "51") (name "/C1_TIM8_CH3") (class "Default")
      (node (ref "MCU1") (pin "98") (pinfunction "PC8_98") (pintype "passive"))
    )
    (net (code "52") (name "/C1_UART5_RX") (class "Default")
      (node (ref "MCU1") (pin "73") (pinfunction "PB12_73") (pintype "passive"))
      (node (ref "R25") (pin "1") (pinfunction "2_1") (pintype "passive"))
      (node (ref "VD2") (pin "2") (pinfunction "64_2") (pintype "passive"))
    )
    (net (code "53") (name "/C1_UART5_TX") (class "Default")
      (node (ref "MCU1") (pin "74") (pinfunction "PB13_74") (pintype "passive"))
      (node (ref "R23") (pin "1") (pinfunction "2_1") (pintype "passive"))
      (node (ref "VD1") (pin "2") (pinfunction "64_2") (pintype "passive"))
    )
    (net (code "54") (name "/C1_UART7_CTS") (class "Default")
      (node (ref "CN6") (pin "3") (pintype "passive"))
      (node (ref "MCU1") (pin "21") (pinfunction "PF9_21") (pintype "passive"))
    )
    (net (code "55") (name "/C1_UART7_RX") (class "Default")
      (node (ref "CN6") (pin "2") (pintype "passive"))
      (node (ref "MCU1") (pin "18") (pinfunction "PF6_18") (pintype "passive"))
    )
    (net (code "56") (name "/C1_UART7_TX") (class "Default")
      (node (ref "CN6") (pin "1") (pintype "passive"))
      (node (ref "MCU1") (pin "19") (pinfunction "PF7_19") (pintype "passive"))
    )
    (net (code "57") (name "/C1_UART8_RX") (class "Default")
      (node (ref "MCU1") (pin "141") (pinfunction "PE0_141") (pintype "passive"))
    )
    (net (code "58") (name "/C1_UART8_TX") (class "Default")
      (node (ref "MCU1") (pin "142") (pinfunction "PE1_142") (pintype "passive"))
    )
    (net (code "59") (name "/C1_VCAP_1") (class "Default")
      (node (ref "C5") (pin "1") (pinfunction "61_1") (pintype "passive"))
      (node (ref "MCU1") (pin "71") (pinfunction "VCAP1_71") (pintype "passive"))
    )
    (net (code "60") (name "/C1_VCAP_2") (class "Default")
      (node (ref "C6") (pin "1") (pinfunction "61_1") (pintype "passive"))
      (node (ref "MCU1") (pin "106") (pinfunction "VCAP2_106") (pintype "passive"))
    )
    (net (code "61") (name "/DEBUG_LED1") (class "Default")
      (node (ref "MCU1") (pin "123") (pinfunction "PD7_123") (pintype "passive"))
      (node (ref "R35") (pin "2") (pinfunction "2_2") (pintype "passive"))
    )
    (net (code "62") (name "/DRV1_EN") (class "Default")
      (node (ref "MCU1") (pin "87") (pinfunction "PG2_87") (pintype "passive"))
    )
    (net (code "63") (name "/DRV2_EN") (class "Default")
      (node (ref "MCU1") (pin "88") (pinfunction "PG3_88") (pintype "passive"))
    )
    (net (code "64") (name "/DRV3_EN") (class "Default")
      (node (ref "MCU1") (pin "89") (pinfunction "PG4_89") (pintype "passive"))
    )
    (net (code "65") (name "/DRV4_EN") (class "Default")
      (node (ref "MCU1") (pin "90") (pinfunction "PG5_90") (pintype "passive"))
    )
    (net (code "66") (name "/DRV5_EN") (class "Default")
      (node (ref "MCU1") (pin "91") (pinfunction "PG6_91") (pintype "passive"))
    )
    (net (code "67") (name "/DRV6_EN") (class "Default")
      (node (ref "MCU1") (pin "92") (pinfunction "PG7_92") (pintype "passive"))
    )
    (net (code "68") (name "/EEPROM_WP") (class "Default")
      (node (ref "MCU1") (pin "135") (pinfunction "PB5_135") (pintype "passive"))
      (node (ref "R4") (pin "1") (pinfunction "2_1") (pintype "passive"))
      (node (ref "U1") (pin "7") (pinfunction "WP_7") (pintype "passive"))
    )
    (net (code "69") (name "/EXT_IN1") (class "Default")
      (node (ref "CN9") (pin "1") (pintype "passive"))
      (node (ref "OC2") (pin "7") (pinfunction "1_7") (pintype "passive"))
    )
    (net (code "70") (name "/EXT_IN2") (class "Default")
      (node (ref "CN9") (pin "2") (pintype "passive"))
      (node (ref "OC2") (pin "5") (pinfunction "1_5") (pintype "passive"))
    )
    (net (code "71") (name "/EXT_IN3") (class "Default")
      (node (ref "CN10") (pin "2") (pintype "passive"))
      (node (ref "OC2") (pin "3") (pinfunction "1_3") (pintype "passive"))
    )
    (net (code "72") (name "/EXT_IN4") (class "Default")
      (node (ref "CN11") (pin "2") (pintype "passive"))
      (node (ref "OC2") (pin "1") (pinfunction "1_1") (pintype "passive"))
    )
    (net (code "73") (name "/GND") (class "Default")
      (node (ref "C1") (pin "1") (pinfunction "61_1") (pintype "passive"))
      (node (ref "C10") (pin "2") (pinfunction "62_2") (pintype "passive"))
      (node (ref "C11") (pin "2") (pinfunction "62_2") (pintype "passive"))
      (node (ref "C12") (pin "1") (pinfunction "61_1") (pintype "passive"))
      (node (ref "C13") (pin "1") (pinfunction "61_1") (pintype "passive"))
      (node (ref "C14") (pin "2") (pinfunction "62_2") (pintype "passive"))
      (node (ref "C15") (pin "1") (pinfunction "61_1") (pintype "passive"))
      (node (ref "C16") (pin "1") (pinfunction "61_1") (pintype "passive"))
      (node (ref "C17") (pin "1") (pinfunction "61_1") (pintype "passive"))
      (node (ref "C18") (pin "2") (pinfunction "62_2") (pintype "passive"))
      (node (ref "C19") (pin "2") (pinfunction "62_2") (pintype "passive"))
      (node (ref "C2") (pin "1") (pinfunction "61_1") (pintype "passive"))
      (node (ref "C20") (pin "2") (pinfunction "62_2") (pintype "passive"))
      (node (ref "C21") (pin "2") (pinfunction "62_2") (pintype "passive"))
      (node (ref "C22") (pin "1") (pinfunction "61_1") (pintype "passive"))
      (node (ref "C23") (pin "1") (pinfunction "61_1") (pintype "passive"))
      (node (ref "C24") (pin "1") (pinfunction "61_1") (pintype "passive"))
      (node (ref "C25") (pin "1") (pinfunction "61_1") (pintype "passive"))
      (node (ref "C26") (pin "1") (pinfunction "61_1") (pintype "passive"))
      (node (ref "C27") (pin "1") (pinfunction "61_1") (pintype "passive"))
      (node (ref "C28") (pin "2") (pinfunction "62_2") (pintype "passive"))
      (node (ref "C29") (pin "1") (pinfunction "61_1") (pintype "passive"))
      (node (ref "C3") (pin "1") (pinfunction "61_1") (pintype "passive"))
      (node (ref "C30") (pin "1") (pinfunction "61_1") (pintype "passive"))
      (node (ref "C31") (pin "1") (pinfunction "61_1") (pintype "passive"))
      (node (ref "C32") (pin "1") (pinfunction "61_1") (pintype "passive"))
      (node (ref "C33") (pin "1") (pinfunction "61_1") (pintype "passive"))
      (node (ref "C34") (pin "1") (pinfunction "61_1") (pintype "passive"))
      (node (ref "C35") (pin "1") (pinfunction "61_1") (pintype "passive"))
      (node (ref "C36") (pin "1") (pinfunction "61_1") (pintype "passive"))
      (node (ref "C37") (pin "1") (pinfunction "61_1") (pintype "passive"))
      (node (ref "C38") (pin "1") (pinfunction "61_1") (pintype "passive"))
      (node (ref "C39") (pin "1") (pinfunction "61_1") (pintype "passive"))
      (node (ref "C4") (pin "1") (pinfunction "61_1") (pintype "passive"))
      (node (ref "C40") (pin "1") (pinfunction "61_1") (pintype "passive"))
      (node (ref "C41") (pin "1") (pinfunction "61_1") (pintype "passive"))
      (node (ref "C42") (pin "1") (pinfunction "61_1") (pintype "passive"))
      (node (ref "C43") (pin "1") (pinfunction "61_1") (pintype "passive"))
      (node (ref "C44") (pin "1") (pinfunction "61_1") (pintype "passive"))
      (node (ref "C45") (pin "1") (pinfunction "61_1") (pintype "passive"))
      (node (ref "C5") (pin "2") (pinfunction "62_2") (pintype "passive"))
      (node (ref "C6") (pin "2") (pinfunction "62_2") (pintype "passive"))
      (node (ref "C7") (pin "1") (pinfunction "61_1") (pintype "passive"))
      (node (ref "C8") (pin "2") (pinfunction "62_2") (pintype "passive"))
      (node (ref "C9") (pin "2") (pinfunction "62_2") (pintype "passive"))
      (node (ref "CN1") (pin "3") (pintype "passive"))
      (node (ref "CN1") (pin "4") (pintype "passive"))
      (node (ref "CN12") (pin "5") (pintype "passive"))
      (node (ref "CN14") (pin "4") (pintype "passive"))
      (node (ref "CN16") (pin "2") (pintype "passive"))
      (node (ref "CN2") (pin "3") (pintype "passive"))
      (node (ref "CN2") (pin "4") (pintype "passive"))
      (node (ref "CN3") (pin "2") (pintype "passive"))
      (node (ref "CN4") (pin "3") (pintype "passive"))
      (node (ref "CN4") (pin "4") (pintype "passive"))
      (node (ref "CN5") (pin "2") (pintype "passive"))
      (node (ref "CN6") (pin "5") (pintype "passive"))
      (node (ref "CN7") (pin "4") (pintype "passive"))
      (node (ref "DISPLAY1") (pin "7") (pinfunction "GND_7") (pintype "passive"))
      (node (ref "GB1") (pin "1") (pinfunction "+_1") (pintype "passive"))
      (node (ref "LED1") (pin "2") (pinfunction "6_2") (pintype "passive"))
      (node (ref "LED2") (pin "2") (pinfunction "6_2") (pintype "passive"))
      (node (ref "LED3") (pin "2") (pinfunction "6_2") (pintype "passive"))
      (node (ref "LED4") (pin "2") (pinfunction "6_2") (pintype "passive"))
      (node (ref "MCU1") (pin "107") (pinfunction "VSS_107") (pintype "passive"))
      (node (ref "MCU1") (pin "120") (pinfunction "VSS_120") (pintype "passive"))
      (node (ref "MCU1") (pin "130") (pinfunction "VSS_130") (pintype "passive"))
      (node (ref "MCU1") (pin "16") (pinfunction "VSS_16") (pintype "passive"))
      (node (ref "MCU1") (pin "31") (pinfunction "VSSA_31") (pintype "passive"))
      (node (ref "MCU1") (pin "38") (pinfunction "VSS_38") (pintype "passive"))
      (node (ref "MCU1") (pin "51") (pinfunction "VSS_51") (pintype "passive"))
      (node (ref "MCU1") (pin "61") (pinfunction "VSS_61") (pintype "passive"))
      (node (ref "MCU1") (pin "83") (pinfunction "VSS_83") (pintype "passive"))
      (node (ref "MCU1") (pin "94") (pinfunction "VSS_94") (pintype "passive"))
      (node (ref "R11") (pin "1") (pinfunction "2_1") (pintype "passive"))
      (node (ref "R13") (pin "1") (pinfunction "2_1") (pintype "passive"))
      (node (ref "R15") (pin "1") (pinfunction "2_1") (pintype "passive"))
      (node (ref "R17") (pin "1") (pinfunction "2_1") (pintype "passive"))
      (node (ref "R19") (pin "1") (pinfunction "2_1") (pintype "passive"))
      (node (ref "R21") (pin "1") (pinfunction "2_1") (pintype "passive"))
      (node (ref "R33") (pin "1") (pinfunction "2_1") (pintype "passive"))
      (node (ref "R5") (pin "1") (pinfunction "2_1") (pintype "passive"))
      (node (ref "R7") (pin "1") (pinfunction "2_1") (pintype "passive"))
      (node (ref "R9") (pin "1") (pinfunction "2_1") (pintype "passive"))
      (node (ref "SB1") (pin "1") (pintype "passive"))
      (node (ref "SB2") (pin "1") (pintype "passive"))
      (node (ref "SB3") (pin "1") (pintype "passive"))
      (node (ref "SB6") (pin "1") (pintype "passive"))
      (node (ref "SW1") (pin "1") (pinfunction "Q1_1") (pintype "passive"))
      (node (ref "SW2") (pin "3") (pinfunction "Q2_3") (pintype "passive"))
      (node (ref "SW3") (pin "3") (pinfunction "Q2_3") (pintype "passive"))
      (node (ref "SW4") (pin "3") (pinfunction "Q2_3") (pintype "passive"))
      (node (ref "U1") (pin "4") (pinfunction "GND_4") (pintype "passive"))
      (node (ref "U2") (pin "2") (pinfunction "ADJ_2") (pintype "passive"))
      (node (ref "U3") (pin "1") (pinfunction "ADJ_1") (pintype "passive"))
      (node (ref "U4") (pin "18") (pinfunction "GND_18") (pintype "passive"))
      (node (ref "U4") (pin "20") (pinfunction "RESV_20") (pintype "passive"))
      (node (ref "VD1") (pin "1") (pinfunction "63_1") (pintype "passive"))
      (node (ref "VD2") (pin "1") (pinfunction "63_1") (pintype "passive"))
      (node (ref "VT1") (pin "3") (pintype "passive"))
      (node (ref "VT2") (pin "3") (pintype "passive"))
      (node (ref "VT3") (pin "3") (pintype "passive"))
      (node (ref "VT4") (pin "1") (pinfunction "G_1") (pintype "passive"))
    )
    (net (code "74") (name "/GND_EXT") (class "Default")
      (node (ref "CN10") (pin "4") (pintype "passive"))
      (node (ref "CN11") (pin "4") (pintype "passive"))
      (node (ref "CN8") (pin "4") (pintype "passive"))
      (node (ref "CN9") (pin "4") (pintype "passive"))
      (node (ref "R10") (pin "2") (pinfunction "2_2") (pintype "passive"))
      (node (ref "R12") (pin "2") (pinfunction "2_2") (pintype "passive"))
      (node (ref "R14") (pin "2") (pinfunction "2_2") (pintype "passive"))
      (node (ref "R16") (pin "2") (pinfunction "2_2") (pintype "passive"))
      (node (ref "R18") (pin "2") (pinfunction "2_2") (pintype "passive"))
      (node (ref "R20") (pin "2") (pinfunction "2_2") (pintype "passive"))
      (node (ref "R6") (pin "2") (pinfunction "2_2") (pintype "passive"))
      (node (ref "R8") (pin "2") (pinfunction "2_2") (pintype "passive"))
    )
    (net (code "75") (name "/LCD_A0") (class "Default")
      (node (ref "DISPLAY1") (pin "4") (pinfunction "A0_4") (pintype "passive"))
      (node (ref "MCU1") (pin "126") (pinfunction "PG11_126") (pintype "passive"))
    )
    (net (code "76") (name "/LCD_CS") (class "Default")
      (node (ref "DISPLAY1") (pin "6") (pinfunction "CS_6") (pintype "passive"))
      (node (ref "MCU1") (pin "127") (pinfunction "PG12_127") (pintype "passive"))
    )
    (net (code "77") (name "/LCD_RES") (class "Default")
      (node (ref "DISPLAY1") (pin "5") (pinfunction "RESET_5") (pintype "passive"))
      (node (ref "MCU1") (pin "125") (pinfunction "PG10_125") (pintype "passive"))
    )
    (net (code "78") (name "/L_LIGHT") (class "Default")
      (node (ref "MCU1") (pin "112") (pinfunction "PC11_112") (pintype "passive"))
      (node (ref "R27") (pin "1") (pinfunction "2_1") (pintype "passive"))
    )
    (net (code "79") (name "/MCU_OUT1") (class "Default")
      (node (ref "CN8") (pin "1") (pintype "passive"))
      (node (ref "OC1") (pin "9") (pinfunction "3_9") (pintype "passive"))
      (node (ref "R18") (pin "1") (pinfunction "2_1") (pintype "passive"))
    )
    (net (code "80") (name "/MCU_OUT2") (class "Default")
      (node (ref "CN8") (pin "2") (pintype "passive"))
      (node (ref "OC1") (pin "11") (pinfunction "3_11") (pintype "passive"))
      (node (ref "R14") (pin "1") (pinfunction "2_1") (pintype "passive"))
    )
    (net (code "81") (name "/MCU_OUT3") (class "Default")
      (node (ref "CN10") (pin "1") (pintype "passive"))
      (node (ref "OC1") (pin "13") (pinfunction "3_13") (pintype "passive"))
      (node (ref "R10") (pin "1") (pinfunction "2_1") (pintype "passive"))
    )
    (net (code "82") (name "/MCU_OUT4") (class "Default")
      (node (ref "CN11") (pin "1") (pintype "passive"))
      (node (ref "OC1") (pin "15") (pinfunction "3_15") (pintype "passive"))
      (node (ref "R6") (pin "1") (pinfunction "2_1") (pintype "passive"))
    )
    (net (code "83") (name "/MPU_INT") (class "Default")
      (node (ref "MCU1") (pin "53") (pinfunction "PF13_53") (pintype "passive"))
      (node (ref "U4") (pin "12") (pinfunction "INT_12") (pintype "passive"))
    )
    (net (code "84") (name "/R_LIGHT") (class "Default")
      (node (ref "MCU1") (pin "111") (pinfunction "PC10_111") (pintype "passive"))
      (node (ref "R22") (pin "1") (pinfunction "2_1") (pintype "passive"))
    )
    (net (code "85") (name "/SRP_IN1") (class "Default")
      (node (ref "MCU1") (pin "59") (pinfunction "PE8_59") (pintype "passive"))
      (node (ref "OC2") (pin "15") (pinfunction "3_15") (pintype "passive"))
      (node (ref "R7") (pin "2") (pinfunction "2_2") (pintype "passive"))
    )
    (net (code "86") (name "/SRP_IN2") (class "Default")
      (node (ref "MCU1") (pin "58") (pinfunction "PE7_58") (pintype "passive"))
      (node (ref "OC2") (pin "13") (pinfunction "3_13") (pintype "passive"))
      (node (ref "R11") (pin "2") (pinfunction "2_2") (pintype "passive"))
    )
    (net (code "87") (name "/SRP_IN3") (class "Default")
      (node (ref "MCU1") (pin "57") (pinfunction "PG1_57") (pintype "passive"))
      (node (ref "OC2") (pin "11") (pinfunction "3_11") (pintype "passive"))
      (node (ref "R15") (pin "2") (pinfunction "2_2") (pintype "passive"))
    )
    (net (code "88") (name "/SRP_IN4") (class "Default")
      (node (ref "MCU1") (pin "56") (pinfunction "PG0_56") (pintype "passive"))
      (node (ref "OC2") (pin "9") (pinfunction "3_9") (pintype "passive"))
      (node (ref "R19") (pin "2") (pinfunction "2_2") (pintype "passive"))
    )
    (net (code "89") (name "/SRP_OUT1") (class "Default")
      (node (ref "MCU1") (pin "77") (pinfunction "PD8_77") (pintype "passive"))
      (node (ref "OC1") (pin "1") (pinfunction "1_1") (pintype "passive"))
    )
    (net (code "90") (name "/SRP_OUT2") (class "Default")
      (node (ref "MCU1") (pin "78") (pinfunction "PD9_78") (pintype "passive"))
      (node (ref "OC1") (pin "3") (pinfunction "1_3") (pintype "passive"))
    )
    (net (code "91") (name "/SRP_OUT3") (class "Default")
      (node (ref "MCU1") (pin "79") (pinfunction "PD10_79") (pintype "passive"))
      (node (ref "OC1") (pin "5") (pinfunction "1_5") (pintype "passive"))
    )
    (net (code "92") (name "/SRP_OUT4") (class "Default")
      (node (ref "MCU1") (pin "80") (pinfunction "PD11_80") (pintype "passive"))
      (node (ref "OC1") (pin "7") (pinfunction "1_7") (pintype "passive"))
    )
    (net (code "93") (name "Net-(BUZ1-Pad2)") (class "Default")
      (node (ref "BUZ1") (pin "2") (pintype "passive"))
      (node (ref "R32") (pin "1") (pinfunction "2_1") (pintype "passive"))
      (node (ref "VT3") (pin "1") (pintype "passive"))
    )
    (net (code "94") (name "Net-(C11-61)") (class "Default")
      (node (ref "C11") (pin "1") (pinfunction "61_1") (pintype "passive"))
      (node (ref "R31") (pin "2") (pinfunction "2_2") (pintype "passive"))
      (node (ref "ZQ2") (pin "1") (pinfunction "10_1") (pintype "passive"))
    )
    (net (code "95") (name "Net-(C17-62)") (class "Default")
      (node (ref "C17") (pin "2") (pinfunction "62_2") (pintype "passive"))
      (node (ref "C26") (pin "2") (pinfunction "62_2") (pintype "passive"))
      (node (ref "U4") (pin "13") (pinfunction "VDD_13") (pintype "passive"))
    )
    (net (code "96") (name "Net-(C27-62)") (class "Default")
      (node (ref "C27") (pin "2") (pinfunction "62_2") (pintype "passive"))
      (node (ref "U4") (pin "10") (pinfunction "REGOUT_10") (pintype "passive"))
    )
    (net (code "97") (name "Net-(CN13-Pad1)") (class "Default")
      (node (ref "CN13") (pin "1") (pintype "passive"))
      (node (ref "R24") (pin "2") (pinfunction "2_2") (pintype "passive"))
    )
    (net (code "98") (name "Net-(CN14-Pad1)") (class "Default")
      (node (ref "CN14") (pin "1") (pintype "passive"))
      (node (ref "R23") (pin "2") (pinfunction "2_2") (pintype "passive"))
    )
    (net (code "99") (name "Net-(CN14-Pad2)") (class "Default")
      (node (ref "CN14") (pin "2") (pintype "passive"))
      (node (ref "R25") (pin "2") (pinfunction "2_2") (pintype "passive"))
    )
    (net (code "100") (name "Net-(CN15-Pad1)") (class "Default")
      (node (ref "CN15") (pin "1") (pintype "passive"))
      (node (ref "R28") (pin "2") (pinfunction "2_2") (pintype "passive"))
    )
    (net (code "101") (name "Net-(DISPLAY1-LED)") (class "Default")
      (node (ref "DISPLAY1") (pin "1") (pinfunction "LED_1") (pintype "passive"))
      (node (ref "R29") (pin "2") (pinfunction "2_2") (pintype "passive"))
    )
    (net (code "102") (name "Net-(LED1-5)") (class "Default")
      (node (ref "LED1") (pin "1") (pinfunction "5_1") (pintype "passive"))
      (node (ref "R35") (pin "1") (pinfunction "2_1") (pintype "passive"))
    )
    (net (code "103") (name "Net-(LED2-5)") (class "Default")
      (node (ref "LED2") (pin "1") (pinfunction "5_1") (pintype "passive"))
      (node (ref "R36") (pin "1") (pinfunction "2_1") (pintype "passive"))
    )
    (net (code "104") (name "Net-(LED3-5)") (class "Default")
      (node (ref "LED3") (pin "1") (pinfunction "5_1") (pintype "passive"))
      (node (ref "R39") (pin "1") (pinfunction "2_1") (pintype "passive"))
    )
    (net (code "105") (name "Net-(LED4-5)") (class "Default")
      (node (ref "LED4") (pin "1") (pinfunction "5_1") (pintype "passive"))
      (node (ref "R40") (pin "1") (pinfunction "2_1") (pintype "passive"))
    )
    (net (code "106") (name "Net-(OC1-Pad2)") (class "Default")
      (node (ref "OC1") (pin "2") (pinfunction "2_2") (pintype "passive"))
      (node (ref "R5") (pin "2") (pinfunction "2_2") (pintype "passive"))
    )
    (net (code "107") (name "Net-(OC1B-2)") (class "Default")
      (node (ref "OC1") (pin "4") (pinfunction "2_4") (pintype "passive"))
      (node (ref "R9") (pin "2") (pinfunction "2_2") (pintype "passive"))
    )
    (net (code "108") (name "Net-(OC1C-2)") (class "Default")
      (node (ref "OC1") (pin "6") (pinfunction "2_6") (pintype "passive"))
      (node (ref "R13") (pin "2") (pinfunction "2_2") (pintype "passive"))
    )
    (net (code "109") (name "Net-(OC1D-2)") (class "Default")
      (node (ref "OC1") (pin "8") (pinfunction "2_8") (pintype "passive"))
      (node (ref "R17") (pin "2") (pinfunction "2_2") (pintype "passive"))
    )
    (net (code "110") (name "Net-(OC2-Pad2)") (class "Default")
      (node (ref "OC2") (pin "2") (pinfunction "2_2") (pintype "passive"))
      (node (ref "R8") (pin "1") (pinfunction "2_1") (pintype "passive"))
    )
    (net (code "111") (name "Net-(OC2B-2)") (class "Default")
      (node (ref "OC2") (pin "4") (pinfunction "2_4") (pintype "passive"))
      (node (ref "R12") (pin "1") (pinfunction "2_1") (pintype "passive"))
    )
    (net (code "112") (name "Net-(OC2C-2)") (class "Default")
      (node (ref "OC2") (pin "6") (pinfunction "2_6") (pintype "passive"))
      (node (ref "R16") (pin "1") (pinfunction "2_1") (pintype "passive"))
    )
    (net (code "113") (name "Net-(OC2D-2)") (class "Default")
      (node (ref "OC2") (pin "8") (pinfunction "2_8") (pintype "passive"))
      (node (ref "R20") (pin "1") (pinfunction "2_1") (pintype "passive"))
    )
    (net (code "114") (name "Net-(R22-Pad2)") (class "Default")
      (node (ref "R22") (pin "2") (pinfunction "2_2") (pintype "passive"))
      (node (ref "VT1") (pin "2") (pintype "passive"))
    )
    (net (code "115") (name "Net-(R24-2-Pad1)") (class "Default")
      (node (ref "R24") (pin "1") (pinfunction "2_1") (pintype "passive"))
      (node (ref "VT1") (pin "1") (pintype "passive"))
    )
    (net (code "116") (name "Net-(R27-Pad2)") (class "Default")
      (node (ref "R27") (pin "2") (pinfunction "2_2") (pintype "passive"))
      (node (ref "VT2") (pin "2") (pintype "passive"))
    )
    (net (code "117") (name "Net-(R28-2-Pad1)") (class "Default")
      (node (ref "R28") (pin "1") (pinfunction "2_1") (pintype "passive"))
      (node (ref "VT2") (pin "1") (pintype "passive"))
    )
    (net (code "118") (name "Net-(R30-2-Pad1)") (class "Default")
      (node (ref "R30") (pin "1") (pinfunction "2_1") (pintype "passive"))
      (node (ref "SB4") (pin "2") (pintype "passive"))
      (node (ref "SB5") (pin "2") (pintype "passive"))
    )
    (net (code "119") (name "Net-(R34-Pad2)") (class "Default")
      (node (ref "R34") (pin "2") (pinfunction "2_2") (pintype "passive"))
      (node (ref "VT3") (pin "2") (pintype "passive"))
    )
    (net (code "120") (name "Net-(U1-A0)") (class "Default")
      (node (ref "R3") (pin "1") (pinfunction "2_1") (pintype "passive"))
      (node (ref "SB1") (pin "2") (pintype "passive"))
      (node (ref "U1") (pin "1") (pinfunction "A0_1") (pintype "passive"))
    )
    (net (code "121") (name "Net-(U1-A1)") (class "Default")
      (node (ref "R2") (pin "1") (pinfunction "2_1") (pintype "passive"))
      (node (ref "SB2") (pin "2") (pintype "passive"))
      (node (ref "U1") (pin "2") (pinfunction "A1_2") (pintype "passive"))
    )
    (net (code "122") (name "Net-(U1-A2)") (class "Default")
      (node (ref "R1") (pin "1") (pinfunction "2_1") (pintype "passive"))
      (node (ref "SB3") (pin "2") (pintype "passive"))
      (node (ref "U1") (pin "3") (pinfunction "A2_3") (pintype "passive"))
    )
    (net (code "123") (name "Net-(U4-AD0{slash}SDO)") (class "Default")
      (node (ref "R41") (pin "1") (pinfunction "2_1") (pintype "passive"))
      (node (ref "SB6") (pin "2") (pintype "passive"))
      (node (ref "U4") (pin "9") (pinfunction "AD0/SDO_9") (pintype "passive"))
    )
    (net (code "124") (name "Net-(VT4-D)") (class "Default")
      (node (ref "CN16") (pin "1") (pintype "passive"))
      (node (ref "VT4") (pin "2") (pinfunction "D_2") (pintype "passive"))
    )
    (net (code "125") (name "unconnected-(DISPLAY1-SD_CS-Pad12)") (class "Default")
      (node (ref "DISPLAY1") (pin "12") (pinfunction "SD_CS_12") (pintype "passive+no_connect"))
    )
    (net (code "126") (name "unconnected-(DISPLAY1-SD_MISO-Pad10)") (class "Default")
      (node (ref "DISPLAY1") (pin "10") (pinfunction "SD_MISO_10") (pintype "passive+no_connect"))
    )
    (net (code "127") (name "unconnected-(DISPLAY1-SD_MOSI-Pad11)") (class "Default")
      (node (ref "DISPLAY1") (pin "11") (pinfunction "SD_MOSI_11") (pintype "passive+no_connect"))
    )
    (net (code "128") (name "unconnected-(DISPLAY1-SD_SCK-Pad9)") (class "Default")
      (node (ref "DISPLAY1") (pin "9") (pinfunction "SD_SCK_9") (pintype "passive+no_connect"))
    )
    (net (code "129") (name "unconnected-(MCU1-PA9-Pad101)") (class "Default")
      (node (ref "MCU1") (pin "101") (pinfunction "PA9_101") (pintype "passive+no_connect"))
    )
    (net (code "130") (name "unconnected-(MCU1-PA10-Pad102)") (class "Default")
      (node (ref "MCU1") (pin "102") (pinfunction "PA10_102") (pintype "passive+no_connect"))
    )
    (net (code "131") (name "unconnected-(MCU1-PA11-Pad103)") (class "Default")
      (node (ref "MCU1") (pin "103") (pinfunction "PA11_103") (pintype "passive+no_connect"))
    )
    (net (code "132") (name "unconnected-(MCU1-PA12-Pad104)") (class "Default")
      (node (ref "MCU1") (pin "104") (pinfunction "PA12_104") (pintype "passive+no_connect"))
    )
    (net (code "133") (name "unconnected-(MCU1-PA15-Pad110)") (class "Default")
      (node (ref "MCU1") (pin "110") (pinfunction "PA15_110") (pintype "passive+no_connect"))
    )
    (net (code "134") (name "unconnected-(MCU1-PB2-Pad48)") (class "Default")
      (node (ref "MCU1") (pin "48") (pinfunction "PB2_48") (pintype "passive+no_connect"))
    )
    (net (code "135") (name "unconnected-(MCU1-PB4-Pad134)") (class "Default")
      (node (ref "MCU1") (pin "134") (pinfunction "PB4_134") (pintype "passive+no_connect"))
    )
    (net (code "136") (name "unconnected-(MCU1-PB8-Pad139)") (class "Default")
      (node (ref "MCU1") (pin "139") (pinfunction "PB8_139") (pintype "passive+no_connect"))
    )
    (net (code "137") (name "unconnected-(MCU1-PB9-Pad140)") (class "Default")
      (node (ref "MCU1") (pin "140") (pinfunction "PB9_140") (pintype "passive+no_connect"))
    )
    (net (code "138") (name "unconnected-(MCU1-PB11-Pad70)") (class "Default")
      (node (ref "MCU1") (pin "70") (pinfunction "PB11_70") (pintype "passive+no_connect"))
    )
    (net (code "139") (name "unconnected-(MCU1-PB14-Pad75)") (class "Default")
      (node (ref "MCU1") (pin "75") (pinfunction "PB14_75") (pintype "passive+no_connect"))
    )
    (net (code "140") (name "unconnected-(MCU1-PB15-Pad76)") (class "Default")
      (node (ref "MCU1") (pin "76") (pinfunction "PB15_76") (pintype "passive+no_connect"))
    )
    (net (code "141") (name "unconnected-(MCU1-PC2-Pad28)") (class "Default")
      (node (ref "MCU1") (pin "28") (pinfunction "PC2_28") (pintype "passive+no_connect"))
    )
    (net (code "142") (name "unconnected-(MCU1-PC3-Pad29)") (class "Default")
      (node (ref "MCU1") (pin "29") (pinfunction "PC3_29") (pintype "passive+no_connect"))
    )
    (net (code "143") (name "unconnected-(MCU1-PC4-Pad44)") (class "Default")
      (node (ref "MCU1") (pin "44") (pinfunction "PC4_44") (pintype "passive+no_connect"))
    )
    (net (code "144") (name "unconnected-(MCU1-PC5-Pad45)") (class "Default")
      (node (ref "MCU1") (pin "45") (pinfunction "PC5_45") (pintype "passive+no_connect"))
    )
    (net (code "145") (name "unconnected-(MCU1-PC12-Pad113)") (class "Default")
      (node (ref "MCU1") (pin "113") (pinfunction "PC12_113") (pintype "passive+no_connect"))
    )
    (net (code "146") (name "unconnected-(MCU1-PC13-Pad7)") (class "Default")
      (node (ref "MCU1") (pin "7") (pinfunction "PC13_7") (pintype "passive+no_connect"))
    )
    (net (code "147") (name "unconnected-(MCU1-PD0-Pad114)") (class "Default")
      (node (ref "MCU1") (pin "114") (pinfunction "PD0_114") (pintype "passive+no_connect"))
    )
    (net (code "148") (name "unconnected-(MCU1-PD1-Pad115)") (class "Default")
      (node (ref "MCU1") (pin "115") (pinfunction "PD1_115") (pintype "passive+no_connect"))
    )
    (net (code "149") (name "unconnected-(MCU1-PD2-Pad116)") (class "Default")
      (node (ref "MCU1") (pin "116") (pinfunction "PD2_116") (pintype "passive+no_connect"))
    )
    (net (code "150") (name "unconnected-(MCU1-PD3-Pad117)") (class "Default")
      (node (ref "MCU1") (pin "117") (pinfunction "PD3_117") (pintype "passive+no_connect"))
    )
    (net (code "151") (name "unconnected-(MCU1-PD4-Pad118)") (class "Default")
      (node (ref "MCU1") (pin "118") (pinfunction "PD4_118") (pintype "passive+no_connect"))
    )
    (net (code "152") (name "unconnected-(MCU1-PD5-Pad119)") (class "Default")
      (node (ref "MCU1") (pin "119") (pinfunction "PD5_119") (pintype "passive+no_connect"))
    )
    (net (code "153") (name "unconnected-(MCU1-PD6-Pad122)") (class "Default")
      (node (ref "MCU1") (pin "122") (pinfunction "PD6_122") (pintype "passive+no_connect"))
    )
    (net (code "154") (name "unconnected-(MCU1-PD15-Pad86)") (class "Default")
      (node (ref "MCU1") (pin "86") (pinfunction "PD15_86") (pintype "passive+no_connect"))
    )
    (net (code "155") (name "unconnected-(MCU1-PE2-Pad1)") (class "Default")
      (node (ref "MCU1") (pin "1") (pinfunction "PE2_1") (pintype "passive+no_connect"))
    )
    (net (code "156") (name "unconnected-(MCU1-PE3-Pad2)") (class "Default")
      (node (ref "MCU1") (pin "2") (pinfunction "PE3_2") (pintype "passive+no_connect"))
    )
    (net (code "157") (name "unconnected-(MCU1-PE4-Pad3)") (class "Default")
      (node (ref "MCU1") (pin "3") (pinfunction "PE4_3") (pintype "passive+no_connect"))
    )
    (net (code "158") (name "unconnected-(MCU1-PE5-Pad4)") (class "Default")
      (node (ref "MCU1") (pin "4") (pinfunction "PE5_4") (pintype "passive+no_connect"))
    )
    (net (code "159") (name "unconnected-(MCU1-PE6-Pad5)") (class "Default")
      (node (ref "MCU1") (pin "5") (pinfunction "PE6_5") (pintype "passive+no_connect"))
    )
    (net (code "160") (name "unconnected-(MCU1-PE10-Pad63)") (class "Default")
      (node (ref "MCU1") (pin "63") (pinfunction "PE10_63") (pintype "passive+no_connect"))
    )
    (net (code "161") (name "unconnected-(MCU1-PE12-Pad65)") (class "Default")
      (node (ref "MCU1") (pin "65") (pinfunction "PE12_65") (pintype "passive+no_connect"))
    )
    (net (code "162") (name "unconnected-(MCU1-PE15-Pad68)") (class "Default")
      (node (ref "MCU1") (pin "68") (pinfunction "PE15_68") (pintype "passive+no_connect"))
    )
    (net (code "163") (name "unconnected-(MCU1-PF3-Pad13)") (class "Default")
      (node (ref "MCU1") (pin "13") (pinfunction "PF3_13") (pintype "passive+no_connect"))
    )
    (net (code "164") (name "unconnected-(MCU1-PF4-Pad14)") (class "Default")
      (node (ref "MCU1") (pin "14") (pinfunction "PF4_14") (pintype "passive+no_connect"))
    )
    (net (code "165") (name "unconnected-(MCU1-PF5-Pad15)") (class "Default")
      (node (ref "MCU1") (pin "15") (pinfunction "PF5_15") (pintype "passive+no_connect"))
    )
    (net (code "166") (name "unconnected-(MCU1-PF8-Pad20)") (class "Default")
      (node (ref "MCU1") (pin "20") (pinfunction "PF8_20") (pintype "passive+no_connect"))
    )
    (net (code "167") (name "unconnected-(MCU1-PF10-Pad22)") (class "Default")
      (node (ref "MCU1") (pin "22") (pinfunction "PF10_22") (pintype "passive+no_connect"))
    )
    (net (code "168") (name "unconnected-(MCU1-PF11-Pad49)") (class "Default")
      (node (ref "MCU1") (pin "49") (pinfunction "PF11_49") (pintype "passive+no_connect"))
    )
    (net (code "169") (name "unconnected-(MCU1-PF12-Pad50)") (class "Default")
      (node (ref "MCU1") (pin "50") (pinfunction "PF12_50") (pintype "passive+no_connect"))
    )
    (net (code "170") (name "unconnected-(MCU1-PG8-Pad93)") (class "Default")
      (node (ref "MCU1") (pin "93") (pinfunction "PG8_93") (pintype "passive+no_connect"))
    )
    (net (code "171") (name "unconnected-(MCU1-PG9-Pad124)") (class "Default")
      (node (ref "MCU1") (pin "124") (pinfunction "PG9_124") (pintype "passive+no_connect"))
    )
    (net (code "172") (name "unconnected-(MCU1-PG15-Pad132)") (class "Default")
      (node (ref "MCU1") (pin "132") (pinfunction "PG15_132") (pintype "passive+no_connect"))
    )
    (net (code "173") (name "unconnected-(SW1-Q1-Pad2)") (class "Default")
      (node (ref "SW1") (pin "2") (pinfunction "Q1_2") (pintype "passive"))
    )
    (net (code "174") (name "unconnected-(SW1-Q2-Pad4)") (class "Default")
      (node (ref "SW1") (pin "4") (pinfunction "Q2_4") (pintype "passive"))
    )
    (net (code "175") (name "unconnected-(SW2-Q1-Pad2)") (class "Default")
      (node (ref "SW2") (pin "2") (pinfunction "Q1_2") (pintype "passive"))
    )
    (net (code "176") (name "unconnected-(SW2-Q2-Pad4)") (class "Default")
      (node (ref "SW2") (pin "4") (pinfunction "Q2_4") (pintype "passive"))
    )
    (net (code "177") (name "unconnected-(SW3-Q1-Pad2)") (class "Default")
      (node (ref "SW3") (pin "2") (pinfunction "Q1_2") (pintype "passive"))
    )
    (net (code "178") (name "unconnected-(SW3-Q2-Pad4)") (class "Default")
      (node (ref "SW3") (pin "4") (pinfunction "Q2_4") (pintype "passive"))
    )
    (net (code "179") (name "unconnected-(SW4-Q1-Pad2)") (class "Default")
      (node (ref "SW4") (pin "2") (pinfunction "Q1_2") (pintype "passive"))
    )
    (net (code "180") (name "unconnected-(SW4-Q2-Pad4)") (class "Default")
      (node (ref "SW4") (pin "4") (pinfunction "Q2_4") (pintype "passive"))
    )
    (net (code "181") (name "unconnected-(U4-AUX_CL-Pad7)") (class "Default")
      (node (ref "U4") (pin "7") (pinfunction "AUX_CL_7") (pintype "passive+no_connect"))
    )
    (net (code "182") (name "unconnected-(U4-AUX_DA-Pad21)") (class "Default")
      (node (ref "U4") (pin "21") (pinfunction "AUX_DA_21") (pintype "passive+no_connect"))
    )
    (net (code "183") (name "unconnected-(U4-FSYNC-Pad11)") (class "Default")
      (node (ref "U4") (pin "11") (pinfunction "FSYNC_11") (pintype "passive+no_connect"))
    )
    (net (code "184") (name "unconnected-(U4-NC.-Pad2)") (class "Default")
      (node (ref "U4") (pin "2") (pinfunction "NC._2") (pintype "passive+no_connect"))
    )
    (net (code "185") (name "unconnected-(U4-NC.-Pad3)") (class "Default")
      (node (ref "U4") (pin "3") (pinfunction "NC._3") (pintype "passive+no_connect"))
    )
    (net (code "186") (name "unconnected-(U4-NC.-Pad4)") (class "Default")
      (node (ref "U4") (pin "4") (pinfunction "NC._4") (pintype "passive+no_connect"))
    )
    (net (code "187") (name "unconnected-(U4-NC.-Pad5)") (class "Default")
      (node (ref "U4") (pin "5") (pinfunction "NC._5") (pintype "passive+no_connect"))
    )
    (net (code "188") (name "unconnected-(U4-NC.-Pad6)") (class "Default")
      (node (ref "U4") (pin "6") (pinfunction "NC._6") (pintype "passive+no_connect"))
    )
    (net (code "189") (name "unconnected-(U4-NC.-Pad14)") (class "Default")
      (node (ref "U4") (pin "14") (pinfunction "NC._14") (pintype "passive+no_connect"))
    )
    (net (code "190") (name "unconnected-(U4-NC.-Pad15)") (class "Default")
      (node (ref "U4") (pin "15") (pinfunction "NC._15") (pintype "passive+no_connect"))
    )
    (net (code "191") (name "unconnected-(U4-NC.-Pad16)") (class "Default")
      (node (ref "U4") (pin "16") (pinfunction "NC._16") (pintype "passive+no_connect"))
    )
    (net (code "192") (name "unconnected-(U4-NC.-Pad17)") (class "Default")
      (node (ref "U4") (pin "17") (pinfunction "NC._17") (pintype "passive+no_connect"))
    )
    (net (code "193") (name "unconnected-(U4-RESV-Pad19)") (class "Default")
      (node (ref "U4") (pin "19") (pinfunction "RESV_19") (pintype "passive+no_connect"))
    )
    (net (code "194") (name "unconnected-(U4-nCS-Pad22)") (class "Default")
      (node (ref "U4") (pin "22") (pinfunction "nCS_22") (pintype "passive+no_connect"))
    )
  )
)
